# mbed-cmsis.net
KiCad netlist of a schematic drawn in EAGLE
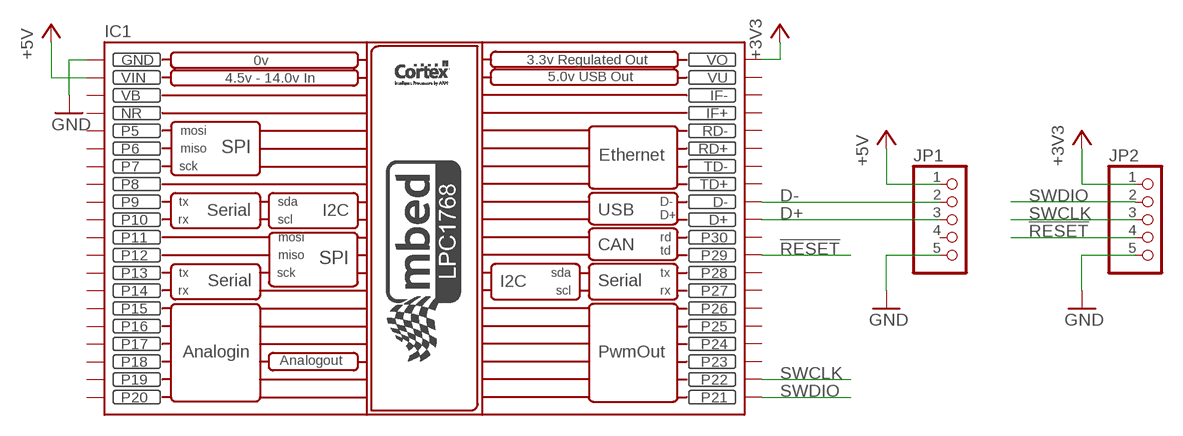
[diagram p0: schematic, sheet 1]

(export (version "E")
  (design (tool "Eeschema 10.0.6"))
  (components
    (comp (ref "IC1")
      (value "MBED_NXP_LPC1768")
      (footprint "eagle-import:MBED-KIT")
      (libsource (lib "eagle-import") (part "MBED_NXP_LPC1768"))
    )
    (comp (ref "JP1")
      (value "PINHD-1X5")
      (footprint "eagle-import:1X05")
      (libsource (lib "eagle-import") (part "PINHD-1X5"))
    )
    (comp (ref "JP2")
      (value "PINHD-1X5")
      (footprint "eagle-import:1X05")
      (libsource (lib "eagle-import") (part "PINHD-1X5"))
    )
  )
  (nets
    (net (code "1") (name "+3V3") (class "Default")
      (node (ref "IC1") (pin "VOUT") (pinfunction "VO_VOUT") (pintype "power_in"))
      (node (ref "JP2") (pin "1") (pinfunction "1_1") (pintype "passive"))
    )
    (net (code "2") (name "+5V") (class "Default")
      (node (ref "IC1") (pin "VIN") (pinfunction "VIN_VIN") (pintype "power_in"))
      (node (ref "JP1") (pin "1") (pinfunction "1_1") (pintype "passive"))
    )
    (net (code "3") (name "/D+") (class "Default")
      (node (ref "IC1") (pin "D+") (pinfunction "D+_D+") (pintype "bidirectional"))
      (node (ref "JP1") (pin "3") (pinfunction "3_3") (pintype "passive"))
    )
    (net (code "4") (name "/D-") (class "Default")
      (node (ref "IC1") (pin "D-") (pinfunction "D-_D-") (pintype "bidirectional"))
      (node (ref "JP1") (pin "2") (pinfunction "2_2") (pintype "passive"))
    )
    (net (code "5") (name "/NR") (class "Default")
      (node (ref "IC1") (pin "NR") (pinfunction "NR_NR") (pintype "power_in"))
    )
    (net (code "6") (name "/SWCLK") (class "Default")
      (node (ref "IC1") (pin "P$22") (pinfunction "P22_P$22") (pintype "bidirectional"))
      (node (ref "JP2") (pin "3") (pinfunction "3_3") (pintype "passive"))
    )
    (net (code "7") (name "/SWDIO") (class "Default")
      (node (ref "IC1") (pin "P$21") (pinfunction "P21_P$21") (pintype "bidirectional"))
      (node (ref "JP2") (pin "2") (pinfunction "2_2") (pintype "passive"))
    )
    (net (code "8") (name "/VB") (class "Default")
      (node (ref "IC1") (pin "VB") (pinfunction "VB_VB") (pintype "power_in"))
    )
    (net (code "9") (name "/VU") (class "Default")
      (node (ref "IC1") (pin "VU") (pinfunction "VU_VU") (pintype "power_in"))
    )
    (net (code "10") (name "/~{RESET}") (class "Default")
      (node (ref "IC1") (pin "P$29") (pinfunction "P29_P$29") (pintype "bidirectional"))
      (node (ref "JP2") (pin "4") (pinfunction "4_4") (pintype "passive"))
    )
    (net (code "11") (name "GND") (class "Default")
      (node (ref "IC1") (pin "GND") (pinfunction "GND_GND") (pintype "power_in"))
      (node (ref "JP1") (pin "5") (pinfunction "5_5") (pintype "passive"))
      (node (ref "JP2") (pin "5") (pinfunction "5_5") (pintype "passive"))
    )
    (net (code "12") (name "unconnected-(IC1-P5-PadP$5)") (class "Default")
      (node (ref "IC1") (pin "P$5") (pinfunction "P5_P$5") (pintype "bidirectional"))
    )
    (net (code "13") (name "unconnected-(IC1-P6-PadP$6)") (class "Default")
      (node (ref "IC1") (pin "P$6") (pinfunction "P6_P$6") (pintype "bidirectional"))
    )
    (net (code "14") (name "unconnected-(IC1-P7-PadP$7)") (class "Default")
      (node (ref "IC1") (pin "P$7") (pinfunction "P7_P$7") (pintype "bidirectional"))
    )
    (net (code "15") (name "unconnected-(IC1-P8-PadP$8)") (class "Default")
      (node (ref "IC1") (pin "P$8") (pinfunction "P8_P$8") (pintype "bidirectional"))
    )
    (net (code "16") (name "unconnected-(IC1-P9-PadP$9)") (class "Default")
      (node (ref "IC1") (pin "P$9") (pinfunction "P9_P$9") (pintype "bidirectional"))
    )
    (net (code "17") (name "unconnected-(IC1-P10-PadP$10)") (class "Default")
      (node (ref "IC1") (pin "P$10") (pinfunction "P10_P$10") (pintype "bidirectional"))
    )
    (net (code "18") (name "unconnected-(IC1-P11-PadP$11)") (class "Default")
      (node (ref "IC1") (pin "P$11") (pinfunction "P11_P$11") (pintype "bidirectional"))
    )
    (net (code "19") (name "unconnected-(IC1-P12-PadP$12)") (class "Default")
      (node (ref "IC1") (pin "P$12") (pinfunction "P12_P$12") (pintype "bidirectional"))
    )
    (net (code "20") (name "unconnected-(IC1-P13-PadP$13)") (class "Default")
      (node (ref "IC1") (pin "P$13") (pinfunction "P13_P$13") (pintype "bidirectional"))
    )
    (net (code "21") (name "unconnected-(IC1-P14-PadP$14)") (class "Default")
      (node (ref "IC1") (pin "P$14") (pinfunction "P14_P$14") (pintype "bidirectional"))
    )
    (net (code "22") (name "unconnected-(IC1-P15-PadP$15)") (class "Default")
      (node (ref "IC1") (pin "P$15") (pinfunction "P15_P$15") (pintype "bidirectional"))
    )
    (net (code "23") (name "unconnected-(IC1-P16-PadP$16)") (class "Default")
      (node (ref "IC1") (pin "P$16") (pinfunction "P16_P$16") (pintype "bidirectional"))
    )
    (net (code "24") (name "unconnected-(IC1-P17-PadP$17)") (class "Default")
      (node (ref "IC1") (pin "P$17") (pinfunction "P17_P$17") (pintype "bidirectional"))
    )
    (net (code "25") (name "unconnected-(IC1-P18-PadP$18)") (class "Default")
      (node (ref "IC1") (pin "P$18") (pinfunction "P18_P$18") (pintype "bidirectional"))
    )
    (net (code "26") (name "unconnected-(IC1-P19-PadP$19)") (class "Default")
      (node (ref "IC1") (pin "P$19") (pinfunction "P19_P$19") (pintype "bidirectional"))
    )
    (net (code "27") (name "unconnected-(IC1-P20-PadP$20)") (class "Default")
      (node (ref "IC1") (pin "P$20") (pinfunction "P20_P$20") (pintype "bidirectional"))
    )
    (net (code "28") (name "unconnected-(IC1-P23-PadP$23)") (class "Default")
      (node (ref "IC1") (pin "P$23") (pinfunction "P23_P$23") (pintype "bidirectional"))
    )
    (net (code "29") (name "unconnected-(IC1-P24-PadP$24)") (class "Default")
      (node (ref "IC1") (pin "P$24") (pinfunction "P24_P$24") (pintype "bidirectional"))
    )
    (net (code "30") (name "unconnected-(IC1-P25-PadP$25)") (class "Default")
      (node (ref "IC1") (pin "P$25") (pinfunction "P25_P$25") (pintype "bidirectional"))
    )
    (net (code "31") (name "unconnected-(IC1-P26-PadP$26)") (class "Default")
      (node (ref "IC1") (pin "P$26") (pinfunction "P26_P$26") (pintype "bidirectional"))
    )
    (net (code "32") (name "unconnected-(IC1-P27-PadP$27)") (class "Default")
      (node (ref "IC1") (pin "P$27") (pinfunction "P27_P$27") (pintype "bidirectional"))
    )
    (net (code "33") (name "unconnected-(IC1-P28-PadP$28)") (class "Default")
      (node (ref "IC1") (pin "P$28") (pinfunction "P28_P$28") (pintype "bidirectional"))
    )
    (net (code "34") (name "unconnected-(IC1-P30-PadP$30)") (class "Default")
      (node (ref "IC1") (pin "P$30") (pinfunction "P30_P$30") (pintype "bidirectional"))
    )
    (net (code "35") (name "unconnected-(IC1-PadIF+)") (class "Default")
      (node (ref "IC1") (pin "IF+") (pinfunction "IF+_IF+") (pintype "bidirectional"))
    )
    (net (code "36") (name "unconnected-(IC1-PadIF-)") (class "Default")
      (node (ref "IC1") (pin "IF-") (pinfunction "IF-_IF-") (pintype "bidirectional"))
    )
    (net (code "37") (name "unconnected-(IC1-PadRD+)") (class "Default")
      (node (ref "IC1") (pin "RD+") (pinfunction "RD+_RD+") (pintype "bidirectional"))
    )
    (net (code "38") (name "unconnected-(IC1-PadRD-)") (class "Default")
      (node (ref "IC1") (pin "RD-") (pinfunction "RD-_RD-") (pintype "bidirectional"))
    )
    (net (code "39") (name "unconnected-(IC1-PadTD+)") (class "Default")
      (node (ref "IC1") (pin "TD+") (pinfunction "TD+_TD+") (pintype "bidirectional"))
    )
    (net (code "40") (name "unconnected-(IC1-PadTD-)") (class "Default")
      (node (ref "IC1") (pin "TD-") (pinfunction "TD-_TD-") (pintype "bidirectional"))
    )
    (net (code "41") (name "unconnected-(JP1-Pad4)") (class "Default")
      (node (ref "JP1") (pin "4") (pinfunction "4_4") (pintype "passive"))
    )
  )
)
